# 3V3_to_2V5.net
KiCad netlist of a schematic drawn in Altium Designer
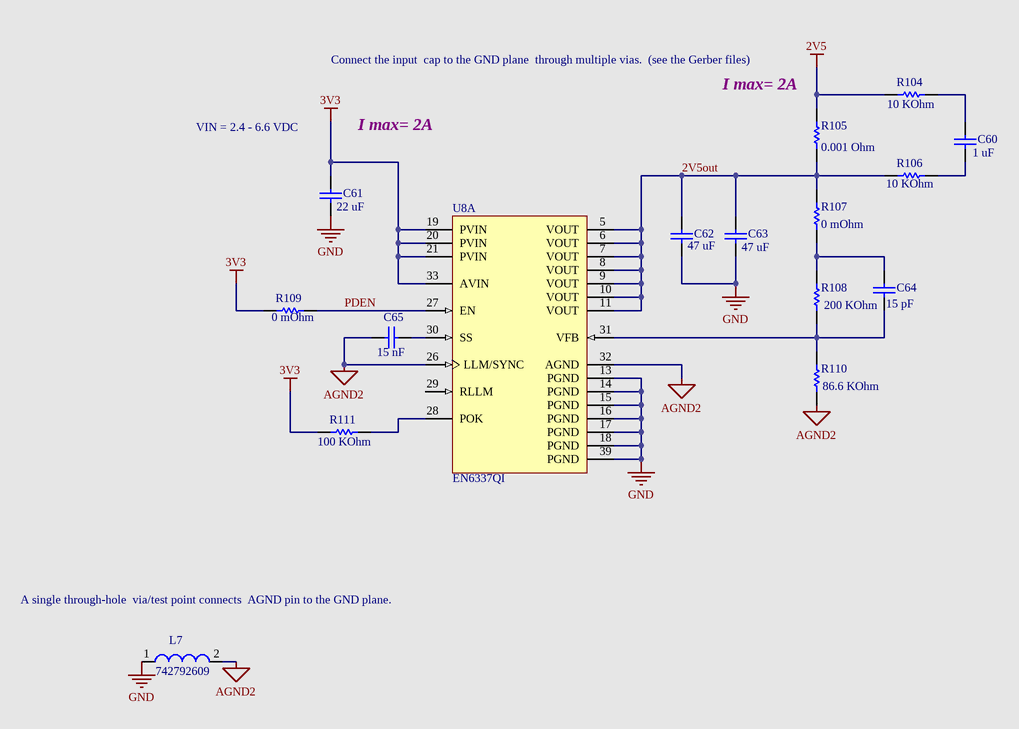
[diagram p0: 3V3_to_2V5.SchDoc]

(export (version "E")
  (design (tool "Eeschema 10.0.6"))
  (components
    (comp (ref "C60")
      (value "CGB2A1X5R1E105K033BC")
      (footprint "CAPC1005X33X10LL5")
      (description "Chip Capacitor, 1 uF, +/- 10%, 25 V, -55 to 85 degC, 0402 (1005 Metric), RoHS, Tape and Reel")
      (fields (field (name "TOLERANCE") "10%") (field (name "CAPACITANCE") "1 uF"))
      (libsource (lib "Altium Content Vault") (part "CAP-NP-2"))
    )
    (comp (ref "C61")
      (value "GRM31CR61E226KE15L")
      (footprint "CAPC3216X180X55ML20T25")
      (description "Chip Capacitor, 22 uF, +/- 10%, 25 V, -55 to 85 degC, 1206 (3216 Metric), RoHS, Tape and Reel")
      (fields (field (name "TOLERANCE") "10%") (field (name "CAPACITANCE") "22 uF"))
      (libsource (lib "") (part "CAP-NP-2_1"))
    )
    (comp (ref "C62")
      (value "C3216X5R1A476M160AB")
      (footprint "CAPC3216X180X20ML20")
      (description "Chip Capacitor, 47 uF, +/- 20%, 10 V, -55 to 85 degC, 1206 (3216 Metric), RoHS, Tape and Reel")
      (fields (field (name "TOLERANCE") "20%") (field (name "CAPACITANCE") "47 uF"))
      (libsource (lib "Altium Content Vault") (part "CAP-NP-2"))
    )
    (comp (ref "C63")
      (value "C3216X5R1A476M160AB")
      (footprint "CAPC3216X180X20ML20")
      (description "Chip Capacitor, 47 uF, +/- 20%, 10 V, -55 to 85 degC, 1206 (3216 Metric), RoHS, Tape and Reel")
      (fields (field (name "TOLERANCE") "20%") (field (name "CAPACITANCE") "47 uF"))
      (libsource (lib "Altium Content Vault") (part "CAP-NP-2"))
    )
    (comp (ref "C64")
      (value "ECJ-0EC1H150J")
      (footprint "CAPC1005X55X20ML5T10")
      (description "Chip Capacitor,15 pF, +/- 5%, 50 V, -55 to 125 degC, 0402 (1005 Metric), RoHS, Tape and Reel")
      (fields (field (name "TOLERANCE") "5%") (field (name "CAPACITANCE") "15 pF"))
      (libsource (lib "Altium Content Vault") (part "CAP-NP-2"))
    )
    (comp (ref "C65")
      (value "VJ0402Y153JXQPW1BC")
      (footprint "CAPC1005X55X23ML05T8")
      (description "Chip Capacitor, 15 nF, +/- 5%, 10 V, -55 to 125 degC, 0402 (1005 Metric), RoHS, Tape and Reel")
      (fields (field (name "CAPACITANCE") "15 nF") (field (name "TOLERANCE") "5%"))
      (libsource (lib "") (part "CAP-NP-2_1"))
    )
    (comp (ref "L7")
      (value "742792609")
      (footprint "SMD-0603")
      (description "SMD EMI Suppression Ferrite Bead WE-CBF, Z = 30 Ohm")
      (libsource (lib "Altium Content Vault") (part "CMP-0220-00193-1"))
    )
    (comp (ref "R104")
      (value "ERJ-2RKF1002X")
      (footprint "RESC1005X40X25NL05T05")
      (description "Chip Resistor, 10 KOhm, +/- 1%, 100 mW, -55 to 155 degC, 0402 (1005 Metric), RoHS, Tape and Reel")
      (fields
        (field (name "TOLERANCE") "1%")
        (field (name "RESISTANCE") "10 KOhm")
        (field (name "MANUFACTURER") "Basic Passives")
      )
      (libsource (lib "Altium Content Vault") (part "RES-2"))
    )
    (comp (ref "R105")
      (value "WSLP12061L000FEA")
      (footprint "RESC3216X89X104LL25T25")
      (description "Chip Resistor, 0.001 Ohm, +/- 1%, 1 W, -65 to 170 degC, 1206 (3216 Metric), RoHS, Tape and Reel")
      (fields (field (name "TOLERANCE") "1%") (field (name "RESISTANCE") "0.001 Ohm"))
      (libsource (lib "Altium Content Vault") (part "RES-2"))
    )
    (comp (ref "R106")
      (value "ERJ-2RKF1002X")
      (footprint "RESC1005X40X25NL05T05")
      (description "Chip Resistor, 10 KOhm, +/- 1%, 100 mW, -55 to 155 degC, 0402 (1005 Metric), RoHS, Tape and Reel")
      (fields
        (field (name "TOLERANCE") "1%")
        (field (name "RESISTANCE") "10 KOhm")
        (field (name "MANUFACTURER") "Basic Passives")
      )
      (libsource (lib "Altium Content Vault") (part "RES-2"))
    )
    (comp (ref "R107")
      (value "ERJ-2GE0R00X")
      (footprint "RESC1005X40X25ML05T05")
      (description "Chip Resistor, 0 mOhm, +/- 5%, 100 mW, -55 to 155 degC, 0402 (1005 Metric), RoHS, Tape and Reel")
      (fields
        (field (name "TOLERANCE") "5%")
        (field (name "RESISTANCE") "0 mOhm")
        (field (name "MANUFACTURER") "Basic Passives")
      )
      (libsource (lib "Altium Content Vault") (part "RES-2"))
    )
    (comp (ref "R108")
      (value "ERJ-2RKF2003X")
      (footprint "RESC1005X40X25NL05T05")
      (description "Chip Resistor, 200 KOhm, +/- 1%, 100 mW, -55 to 155 degC, 0402 (1005 Metric), RoHS, Tape and Reel")
      (fields
        (field (name "RESISTANCE") "200 KOhm")
        (field (name "TOLERANCE") "1%")
        (field (name "MANUFACTURER") "Basic Passives")
      )
      (libsource (lib "Altium Content Vault") (part "RES-2"))
    )
    (comp (ref "R109")
      (value "ERJ-2GE0R00X")
      (footprint "RESC1005X40X25ML05T05")
      (description "Chip Resistor, 0 mOhm, +/- 5%, 100 mW, -55 to 155 degC, 0402 (1005 Metric), RoHS, Tape and Reel")
      (fields
        (field (name "TOLERANCE") "5%")
        (field (name "RESISTANCE") "0 mOhm")
        (field (name "MANUFACTURER") "Basic Passives")
      )
      (libsource (lib "Altium Content Vault") (part "RES-2"))
    )
    (comp (ref "R110")
      (value "ERJ-2RKF8662X")
      (footprint "RESC1005X40X25ML05T05")
      (description "Chip Resistor, 86.6 KOhm, +/- 1%, 100 mW, -55 to 155 degC, 0402 (1005 Metric), RoHS, Tape and Reel")
      (fields
        (field (name "TOLERANCE") "1%")
        (field (name "RESISTANCE") "86.6 KOhm")
        (field (name "MANUFACTURER") "Basic Passives")
      )
      (libsource (lib "Altium Content Vault") (part "RES-2"))
    )
    (comp (ref "R111")
      (value "ERJ-2RKF1003X")
      (footprint "RESC1005X40X25LL05T05")
      (description "Chip Resistor, 100 KOhm, +/- 1%, 100 mW, -55 to 155 degC, 0402 (1005 Metric), RoHS, Tape and Reel")
      (fields
        (field (name "RESISTANCE") "100 KOhm")
        (field (name "TOLERANCE") "1%")
        (field (name "MANUFACTURER") "Basic Passives")
      )
      (libsource (lib "Altium Content Vault") (part "RES-2"))
    )
    (comp (ref "U8")
      (value "EN6337QI")
      (footprint "ALTR-QFN-38_A-190_D1-193_V")
      (libsource (lib "Altium Content Vault") (part "ALTR-EN63X7QI-QFN38"))
    )
  )
  (nets
    (net (code "1") (name "/2V5out") (class "Default")
      (node (ref "C62") (pin "2") (pinfunction "2_2") (pintype "passive"))
      (node (ref "C63") (pin "2") (pinfunction "2_2") (pintype "passive"))
      (node (ref "R105") (pin "1") (pinfunction "1_1") (pintype "passive"))
      (node (ref "R106") (pin "2") (pinfunction "2_2") (pintype "passive"))
      (node (ref "R107") (pin "1") (pinfunction "1_1") (pintype "passive"))
      (node (ref "U8") (pin "10") (pinfunction "VOUT_10") (pintype "power_in"))
      (node (ref "U8") (pin "11") (pinfunction "VOUT_11") (pintype "power_in"))
      (node (ref "U8") (pin "5") (pinfunction "VOUT_5") (pintype "power_in"))
      (node (ref "U8") (pin "6") (pinfunction "VOUT_6") (pintype "power_in"))
      (node (ref "U8") (pin "7") (pinfunction "VOUT_7") (pintype "power_in"))
      (node (ref "U8") (pin "8") (pinfunction "VOUT_8") (pintype "power_in"))
      (node (ref "U8") (pin "9") (pinfunction "VOUT_9") (pintype "power_in"))
    )
    (net (code "2") (name "/PDEN") (class "Default")
      (node (ref "R109") (pin "2") (pinfunction "2_2") (pintype "passive"))
      (node (ref "U8") (pin "27") (pinfunction "EN_27") (pintype "input"))
    )
    (net (code "3") (name "2V5") (class "Default")
      (node (ref "R104") (pin "2") (pinfunction "2_2") (pintype "passive"))
      (node (ref "R105") (pin "2") (pinfunction "2_2") (pintype "passive"))
    )
    (net (code "4") (name "3V3") (class "Default")
      (node (ref "C61") (pin "2") (pinfunction "2_2") (pintype "passive"))
      (node (ref "R109") (pin "1") (pinfunction "1_1") (pintype "passive"))
      (node (ref "R111") (pin "1") (pinfunction "1_1") (pintype "passive"))
      (node (ref "U8") (pin "19") (pinfunction "PVIN_19") (pintype "power_in"))
      (node (ref "U8") (pin "20") (pinfunction "PVIN_20") (pintype "power_in"))
      (node (ref "U8") (pin "21") (pinfunction "PVIN_21") (pintype "power_in"))
      (node (ref "U8") (pin "33") (pinfunction "AVIN_33") (pintype "power_in"))
    )
    (net (code "5") (name "AGND2") (class "Default")
      (node (ref "C65") (pin "1") (pinfunction "1_1") (pintype "passive"))
      (node (ref "L7") (pin "2") (pinfunction "2_2") (pintype "passive"))
      (node (ref "R110") (pin "1") (pinfunction "1_1") (pintype "passive"))
      (node (ref "U8") (pin "26") (pinfunction "LLM/SYNC_26") (pintype "input"))
      (node (ref "U8") (pin "32") (pinfunction "AGND_32") (pintype "power_in"))
    )
    (net (code "6") (name "GND") (class "Default")
      (node (ref "C61") (pin "1") (pinfunction "1_1") (pintype "passive"))
      (node (ref "C62") (pin "1") (pinfunction "1_1") (pintype "passive"))
      (node (ref "C63") (pin "1") (pinfunction "1_1") (pintype "passive"))
      (node (ref "L7") (pin "1") (pinfunction "1_1") (pintype "passive"))
      (node (ref "U8") (pin "13") (pinfunction "PGND_13") (pintype "power_in"))
      (node (ref "U8") (pin "14") (pinfunction "PGND_14") (pintype "power_in"))
      (node (ref "U8") (pin "15") (pinfunction "PGND_15") (pintype "power_in"))
      (node (ref "U8") (pin "16") (pinfunction "PGND_16") (pintype "power_in"))
      (node (ref "U8") (pin "17") (pinfunction "PGND_17") (pintype "power_in"))
      (node (ref "U8") (pin "18") (pinfunction "PGND_18") (pintype "power_in"))
      (node (ref "U8") (pin "39") (pinfunction "PGND_39") (pintype "power_in"))
    )
    (net (code "7") (name "Net-(C60-Pad1)") (class "Default")
      (node (ref "C60") (pin "1") (pinfunction "1_1") (pintype "passive"))
      (node (ref "R106") (pin "1") (pinfunction "1_1") (pintype "passive"))
    )
    (net (code "8") (name "Net-(C60-Pad2)") (class "Default")
      (node (ref "C60") (pin "2") (pinfunction "2_2") (pintype "passive"))
      (node (ref "R104") (pin "1") (pinfunction "1_1") (pintype "passive"))
    )
    (net (code "9") (name "Net-(C64-Pad2)") (class "Default")
      (node (ref "C64") (pin "2") (pinfunction "2_2") (pintype "passive"))
      (node (ref "R107") (pin "2") (pinfunction "2_2") (pintype "passive"))
      (node (ref "R108") (pin "2") (pinfunction "2_2") (pintype "passive"))
    )
    (net (code "10") (name "Net-(U8A-POK)") (class "Default")
      (node (ref "R111") (pin "2") (pinfunction "2_2") (pintype "passive"))
      (node (ref "U8") (pin "28") (pinfunction "POK_28") (pintype "open_collector"))
    )
    (net (code "11") (name "Net-(U8A-SS)") (class "Default")
      (node (ref "C65") (pin "2") (pinfunction "2_2") (pintype "passive"))
      (node (ref "U8") (pin "30") (pinfunction "SS_30") (pintype "input"))
    )
    (net (code "12") (name "Net-(U8A-VFB)") (class "Default")
      (node (ref "C64") (pin "1") (pinfunction "1_1") (pintype "passive"))
      (node (ref "R108") (pin "1") (pinfunction "1_1") (pintype "passive"))
      (node (ref "R110") (pin "2") (pinfunction "2_2") (pintype "passive"))
      (node (ref "U8") (pin "31") (pinfunction "VFB_31") (pintype "input"))
    )
    (net (code "13") (name "unconnected-(U8A-RLLM-Pad29)") (class "Default")
      (node (ref "U8") (pin "29") (pinfunction "RLLM_29") (pintype "input"))
    )
  )
)
